# SCH_Justin-Z-NFC-Card_2024-10-10.net
KiCad netlist of a schematic drawn in EasyEDA
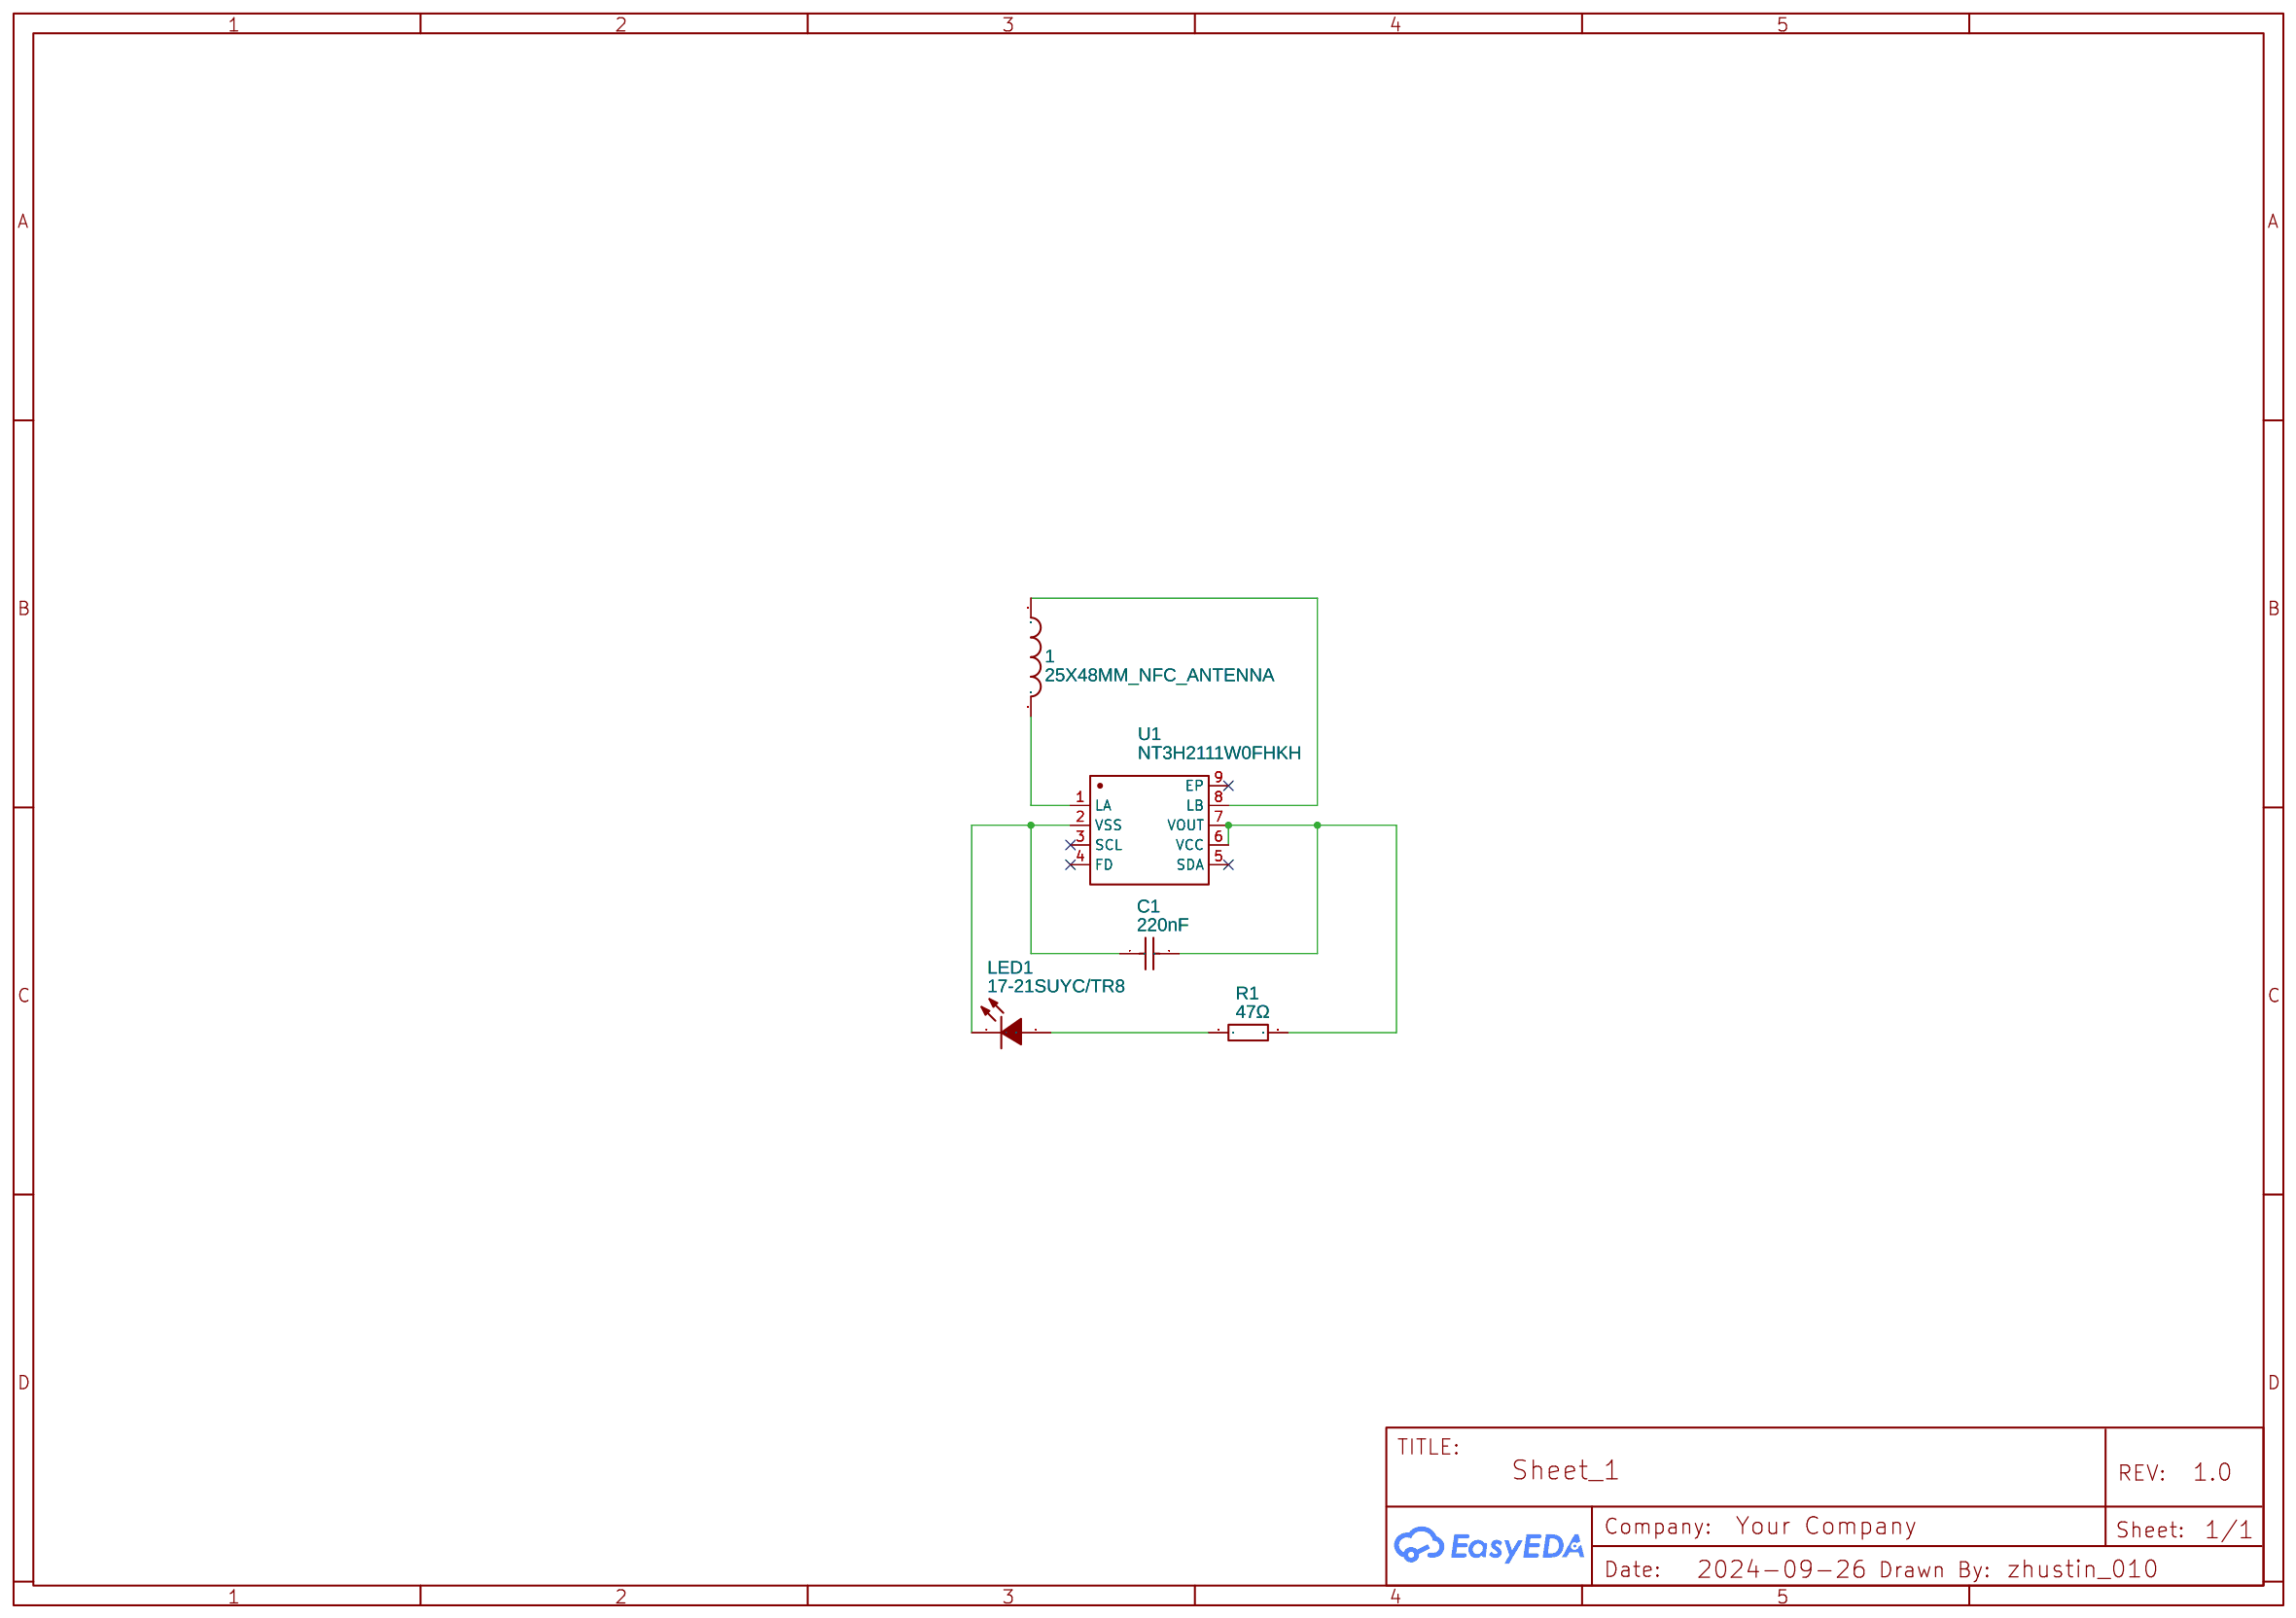
[diagram p0: schematic sheet]

(export (version "E")
  (design (tool "Eeschema 10.0.6"))
  (components
    (comp (ref "1") (value "25X48MM_NFC_ANTENNA") (libsource (lib "") (part "25X48MM_NFC_ANTENNA")))
    (comp (ref "C1")
      (value "220nF")
      (fields
        (field (name "Manufacturer Part") "CL10B224KA8NNNC")
        (field (name "Manufacturer") "SAMSUNG(三星)")
      )
      (libsource (lib "") (part "CL10B224KA8NNNC"))
    )
    (comp (ref "LED1")
      (value "17-21SUYC/TR8")
      (fields (field (name "Manufacturer Part") "KT-0805黄灯") (field (name "Manufacturer") "KENTO"))
      (libsource (lib "") (part "17-21SUYC/TR8"))
    )
    (comp (ref "R1")
      (value "47Ω")
      (fields
        (field (name "Manufacturer Part") "0603WAF470JT5E")
        (field (name "Manufacturer") "UNI-ROYAL(厚声)")
      )
      (libsource (lib "") (part "0603WAF470JT5E"))
    )
    (comp (ref "U1")
      (value "NT3H2111W0FHKH")
      (fields (field (name "Manufacturer") "NXP(恩智浦)"))
      (libsource (lib "") (part "NT3H2111W0FHKH"))
    )
  )
  (nets
    (net (code "1") (name "Net-(LED1-+)") (class "Default")
      (node (ref "LED1") (pin "1") (pinfunction "+_1") (pintype "unspecified"))
      (node (ref "R1") (pin "1") (pinfunction "1_1") (pintype "input"))
    )
    (net (code "2") (name "Net-(LED1--)") (class "Default")
      (node (ref "C1") (pin "1") (pinfunction "1_1") (pintype "input"))
      (node (ref "LED1") (pin "2") (pinfunction "-_2") (pintype "unspecified"))
      (node (ref "U1") (pin "2") (pinfunction "VSS_2") (pintype "unspecified"))
    )
    (net (code "3") (name "Net-(U1-LA)") (class "Default")
      (node (ref "1") (pin "P$2") (pinfunction "P$2_P$2") (pintype "bidirectional"))
      (node (ref "U1") (pin "1") (pinfunction "LA_1") (pintype "unspecified"))
    )
    (net (code "4") (name "Net-(U1-LB)") (class "Default")
      (node (ref "1") (pin "P$1") (pinfunction "P$1_P$1") (pintype "bidirectional"))
      (node (ref "U1") (pin "8") (pinfunction "LB_8") (pintype "unspecified"))
    )
    (net (code "5") (name "Net-(U1-VCC)") (class "Default")
      (node (ref "C1") (pin "2") (pinfunction "2_2") (pintype "input"))
      (node (ref "R1") (pin "2") (pinfunction "2_2") (pintype "input"))
      (node (ref "U1") (pin "6") (pinfunction "VCC_6") (pintype "unspecified"))
      (node (ref "U1") (pin "7") (pinfunction "VOUT_7") (pintype "unspecified"))
    )
    (net (code "6") (name "unconnected-(U1-EP-Pad9)") (class "Default")
      (node (ref "U1") (pin "9") (pinfunction "EP_9") (pintype "unspecified+no_connect"))
    )
    (net (code "7") (name "unconnected-(U1-FD-Pad4)") (class "Default")
      (node (ref "U1") (pin "4") (pinfunction "FD_4") (pintype "unspecified+no_connect"))
    )
    (net (code "8") (name "unconnected-(U1-SCL-Pad3)") (class "Default")
      (node (ref "U1") (pin "3") (pinfunction "SCL_3") (pintype "unspecified+no_connect"))
    )
    (net (code "9") (name "unconnected-(U1-SDA-Pad5)") (class "Default")
      (node (ref "U1") (pin "5") (pinfunction "SDA_5") (pintype "unspecified+no_connect"))
    )
  )
)
